# Board.net
KiCad netlist of a schematic drawn in EAGLE
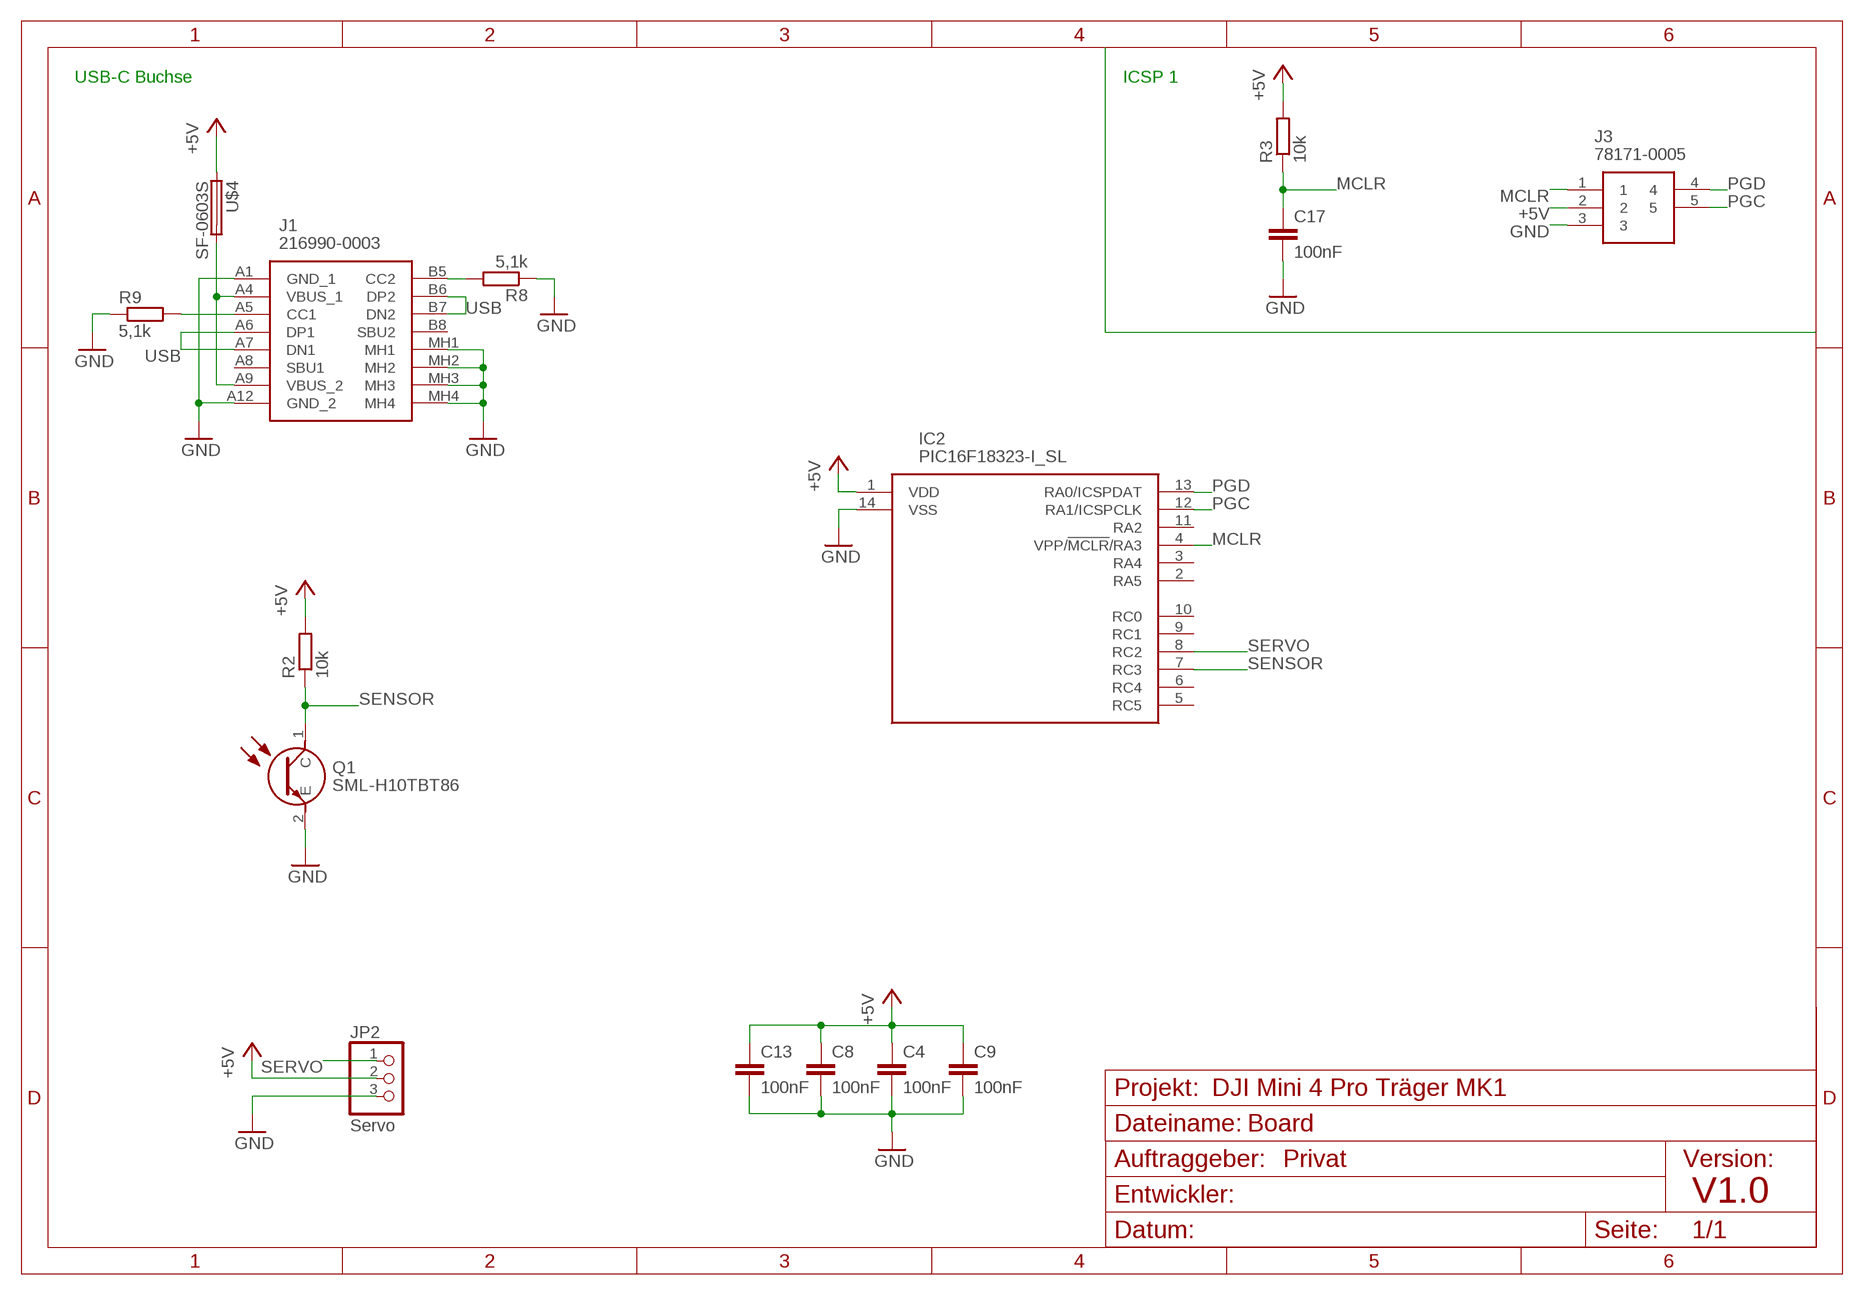
[diagram p0: schematic, sheet 1]

(export (version "E")
  (design (tool "Eeschema 10.0.6"))
  (components
    (comp (ref "C4")
      (value "100nF")
      (footprint "eagle-import:C0805")
      (libsource (lib "eagle-import") (part "C-EUC0805"))
    )
    (comp (ref "C8")
      (value "100nF")
      (footprint "eagle-import:C0805")
      (libsource (lib "eagle-import") (part "C-EUC0805"))
    )
    (comp (ref "C9")
      (value "100nF")
      (footprint "eagle-import:C0805")
      (libsource (lib "eagle-import") (part "C-EUC0805"))
    )
    (comp (ref "C13")
      (value "100nF")
      (footprint "eagle-import:C0805")
      (libsource (lib "eagle-import") (part "C-EUC0805"))
    )
    (comp (ref "C17")
      (value "100nF")
      (footprint "eagle-import:C0805")
      (libsource (lib "eagle-import") (part "C-EUC0805"))
    )
    (comp (ref "IC2")
      (value "PIC16F18323-I_SL")
      (footprint "eagle-import:SOIC127P600X175-14N")
      (fields
        (field (name "MANUFACTURER_PART_NUMBER") "PIC16F18323-I/SL")
        (field (name "MOUSER_PART_NUMBER") "579-PIC16F18323-I/SL")
      )
      (libsource (lib "eagle-import") (part "PIC16F18323-I_SL"))
    )
    (comp (ref "J1")
      (value "216990-0003")
      (footprint "eagle-import:2169900003")
      (fields (field (name "MOUSER_PART_NUMBER") "538-216990-0003"))
      (libsource (lib "eagle-import") (part "216990-0003"))
    )
    (comp (ref "J3")
      (value "78171-0005")
      (footprint "eagle-import:78171-0005")
      (fields (field (name "MOUSER_PART_NUMBER") "538-78171-0005"))
      (libsource (lib "eagle-import") (part "78171-0005"))
    )
    (comp (ref "JP2")
      (value "Servo")
      (footprint "eagle-import:1X03_90")
      (libsource (lib "eagle-import") (part "PINHD-1X3/90"))
    )
    (comp (ref "Q1")
      (value "SML-H10TBT86")
      (footprint "eagle-import:SMLH10TBT86")
      (fields (field (name "MOUSER_PART_NUMBER") "755-SML-H10TBT86"))
      (libsource (lib "eagle-import") (part "SML-H10TBT86"))
    )
    (comp (ref "R2")
      (value "10k")
      (footprint "eagle-import:R0805")
      (libsource (lib "eagle-import") (part "R-EU_R0805"))
    )
    (comp (ref "R3")
      (value "10k")
      (footprint "eagle-import:R0805")
      (libsource (lib "eagle-import") (part "R-EU_R0805"))
    )
    (comp (ref "R8")
      (value "5,1k")
      (footprint "eagle-import:R0805")
      (libsource (lib "eagle-import") (part "R-EU_R0805"))
    )
    (comp (ref "R9")
      (value "5,1k")
      (footprint "eagle-import:R0805")
      (libsource (lib "eagle-import") (part "R-EU_R0805"))
    )
    (comp (ref "U$4")
      (value "SF-0603S")
      (footprint "eagle-import:R0603")
      (libsource (lib "eagle-import") (part "SF-0603S"))
    )
  )
  (nets
    (net (code "1") (name "+5V") (class "Default")
      (node (ref "C13") (pin "1") (pinfunction "1_1") (pintype "passive"))
      (node (ref "C4") (pin "1") (pinfunction "1_1") (pintype "passive"))
      (node (ref "C8") (pin "1") (pinfunction "1_1") (pintype "passive"))
      (node (ref "C9") (pin "1") (pinfunction "1_1") (pintype "passive"))
      (node (ref "IC2") (pin "1") (pinfunction "VDD_1") (pintype "power_in"))
      (node (ref "J3") (pin "2") (pinfunction "2_2") (pintype "bidirectional"))
      (node (ref "JP2") (pin "2") (pinfunction "2_2") (pintype "passive"))
      (node (ref "R2") (pin "2") (pinfunction "2_2") (pintype "passive"))
      (node (ref "R3") (pin "2") (pinfunction "2_2") (pintype "passive"))
      (node (ref "U$4") (pin "1") (pinfunction "1_1") (pintype "passive"))
    )
    (net (code "2") (name "/MCLR") (class "Default")
      (node (ref "C17") (pin "1") (pinfunction "1_1") (pintype "passive"))
      (node (ref "IC2") (pin "4") (pinfunction "VPP/~{MCLR}/RA3_4") (pintype "input"))
      (node (ref "J3") (pin "1") (pinfunction "1_1") (pintype "bidirectional"))
      (node (ref "R3") (pin "1") (pinfunction "1_1") (pintype "passive"))
    )
    (net (code "3") (name "/PGC") (class "Default")
      (node (ref "IC2") (pin "12") (pinfunction "RA1/ICSPCLK_12") (pintype "bidirectional"))
      (node (ref "J3") (pin "5") (pinfunction "5_5") (pintype "bidirectional"))
    )
    (net (code "4") (name "/PGD") (class "Default")
      (node (ref "IC2") (pin "13") (pinfunction "RA0/ICSPDAT_13") (pintype "bidirectional"))
      (node (ref "J3") (pin "4") (pinfunction "4_4") (pintype "bidirectional"))
    )
    (net (code "5") (name "/SENSOR") (class "Default")
      (node (ref "IC2") (pin "7") (pinfunction "RC3_7") (pintype "bidirectional"))
      (node (ref "Q1") (pin "1") (pinfunction "C_1") (pintype "bidirectional"))
      (node (ref "R2") (pin "1") (pinfunction "1_1") (pintype "passive"))
    )
    (net (code "6") (name "/SERVO") (class "Default")
      (node (ref "IC2") (pin "8") (pinfunction "RC2_8") (pintype "bidirectional"))
      (node (ref "JP2") (pin "1") (pinfunction "1_1") (pintype "passive"))
    )
    (net (code "7") (name "/USB") (class "Default")
      (node (ref "J1") (pin "A6") (pinfunction "DP1_A6") (pintype "bidirectional"))
      (node (ref "J1") (pin "A7") (pinfunction "DN1_A7") (pintype "bidirectional"))
      (node (ref "J1") (pin "B6") (pinfunction "DP2_B6") (pintype "bidirectional"))
      (node (ref "J1") (pin "B7") (pinfunction "DN2_B7") (pintype "bidirectional"))
    )
    (net (code "8") (name "GND") (class "Default")
      (node (ref "C13") (pin "2") (pinfunction "2_2") (pintype "passive"))
      (node (ref "C17") (pin "2") (pinfunction "2_2") (pintype "passive"))
      (node (ref "C4") (pin "2") (pinfunction "2_2") (pintype "passive"))
      (node (ref "C8") (pin "2") (pinfunction "2_2") (pintype "passive"))
      (node (ref "C9") (pin "2") (pinfunction "2_2") (pintype "passive"))
      (node (ref "IC2") (pin "14") (pinfunction "VSS_14") (pintype "power_in"))
      (node (ref "J1") (pin "A1") (pinfunction "GND_1_A1") (pintype "bidirectional"))
      (node (ref "J1") (pin "A12") (pinfunction "GND_2_A12") (pintype "bidirectional"))
      (node (ref "J1") (pin "MH1") (pinfunction "MH1_MH1") (pintype "bidirectional"))
      (node (ref "J1") (pin "MH2") (pinfunction "MH2_MH2") (pintype "bidirectional"))
      (node (ref "J1") (pin "MH3") (pinfunction "MH3_MH3") (pintype "bidirectional"))
      (node (ref "J1") (pin "MH4") (pinfunction "MH4_MH4") (pintype "bidirectional"))
      (node (ref "J3") (pin "3") (pinfunction "3_3") (pintype "bidirectional"))
      (node (ref "JP2") (pin "3") (pinfunction "3_3") (pintype "passive"))
      (node (ref "Q1") (pin "2") (pinfunction "E_2") (pintype "bidirectional"))
      (node (ref "R8") (pin "1") (pinfunction "1_1") (pintype "passive"))
      (node (ref "R9") (pin "1") (pinfunction "1_1") (pintype "passive"))
    )
    (net (code "9") (name "Net-(J1-CC1)") (class "Default")
      (node (ref "J1") (pin "A5") (pinfunction "CC1_A5") (pintype "bidirectional"))
      (node (ref "R9") (pin "2") (pinfunction "2_2") (pintype "passive"))
    )
    (net (code "10") (name "Net-(J1-CC2)") (class "Default")
      (node (ref "J1") (pin "B5") (pinfunction "CC2_B5") (pintype "bidirectional"))
      (node (ref "R8") (pin "2") (pinfunction "2_2") (pintype "passive"))
    )
    (net (code "11") (name "Net-(J1-VBUS_1)") (class "Default")
      (node (ref "J1") (pin "A4") (pinfunction "VBUS_1_A4") (pintype "bidirectional"))
      (node (ref "J1") (pin "A9") (pinfunction "VBUS_2_A9") (pintype "bidirectional"))
      (node (ref "U$4") (pin "2") (pinfunction "2_2") (pintype "passive"))
    )
    (net (code "12") (name "unconnected-(IC2-RA2-Pad11)") (class "Default")
      (node (ref "IC2") (pin "11") (pinfunction "RA2_11") (pintype "bidirectional"))
    )
    (net (code "13") (name "unconnected-(IC2-RA4-Pad3)") (class "Default")
      (node (ref "IC2") (pin "3") (pinfunction "RA4_3") (pintype "bidirectional"))
    )
    (net (code "14") (name "unconnected-(IC2-RA5-Pad2)") (class "Default")
      (node (ref "IC2") (pin "2") (pinfunction "RA5_2") (pintype "bidirectional"))
    )
    (net (code "15") (name "unconnected-(IC2-RC0-Pad10)") (class "Default")
      (node (ref "IC2") (pin "10") (pinfunction "RC0_10") (pintype "bidirectional"))
    )
    (net (code "16") (name "unconnected-(IC2-RC1-Pad9)") (class "Default")
      (node (ref "IC2") (pin "9") (pinfunction "RC1_9") (pintype "bidirectional"))
    )
    (net (code "17") (name "unconnected-(IC2-RC4-Pad6)") (class "Default")
      (node (ref "IC2") (pin "6") (pinfunction "RC4_6") (pintype "bidirectional"))
    )
    (net (code "18") (name "unconnected-(IC2-RC5-Pad5)") (class "Default")
      (node (ref "IC2") (pin "5") (pinfunction "RC5_5") (pintype "bidirectional"))
    )
    (net (code "19") (name "unconnected-(J1-SBU1-PadA8)") (class "Default")
      (node (ref "J1") (pin "A8") (pinfunction "SBU1_A8") (pintype "bidirectional"))
    )
    (net (code "20") (name "unconnected-(J1-SBU2-PadB8)") (class "Default")
      (node (ref "J1") (pin "B8") (pinfunction "SBU2_B8") (pintype "bidirectional"))
    )
  )
)
